# TOP.net
KiCad netlist of a schematic drawn in Altium Designer
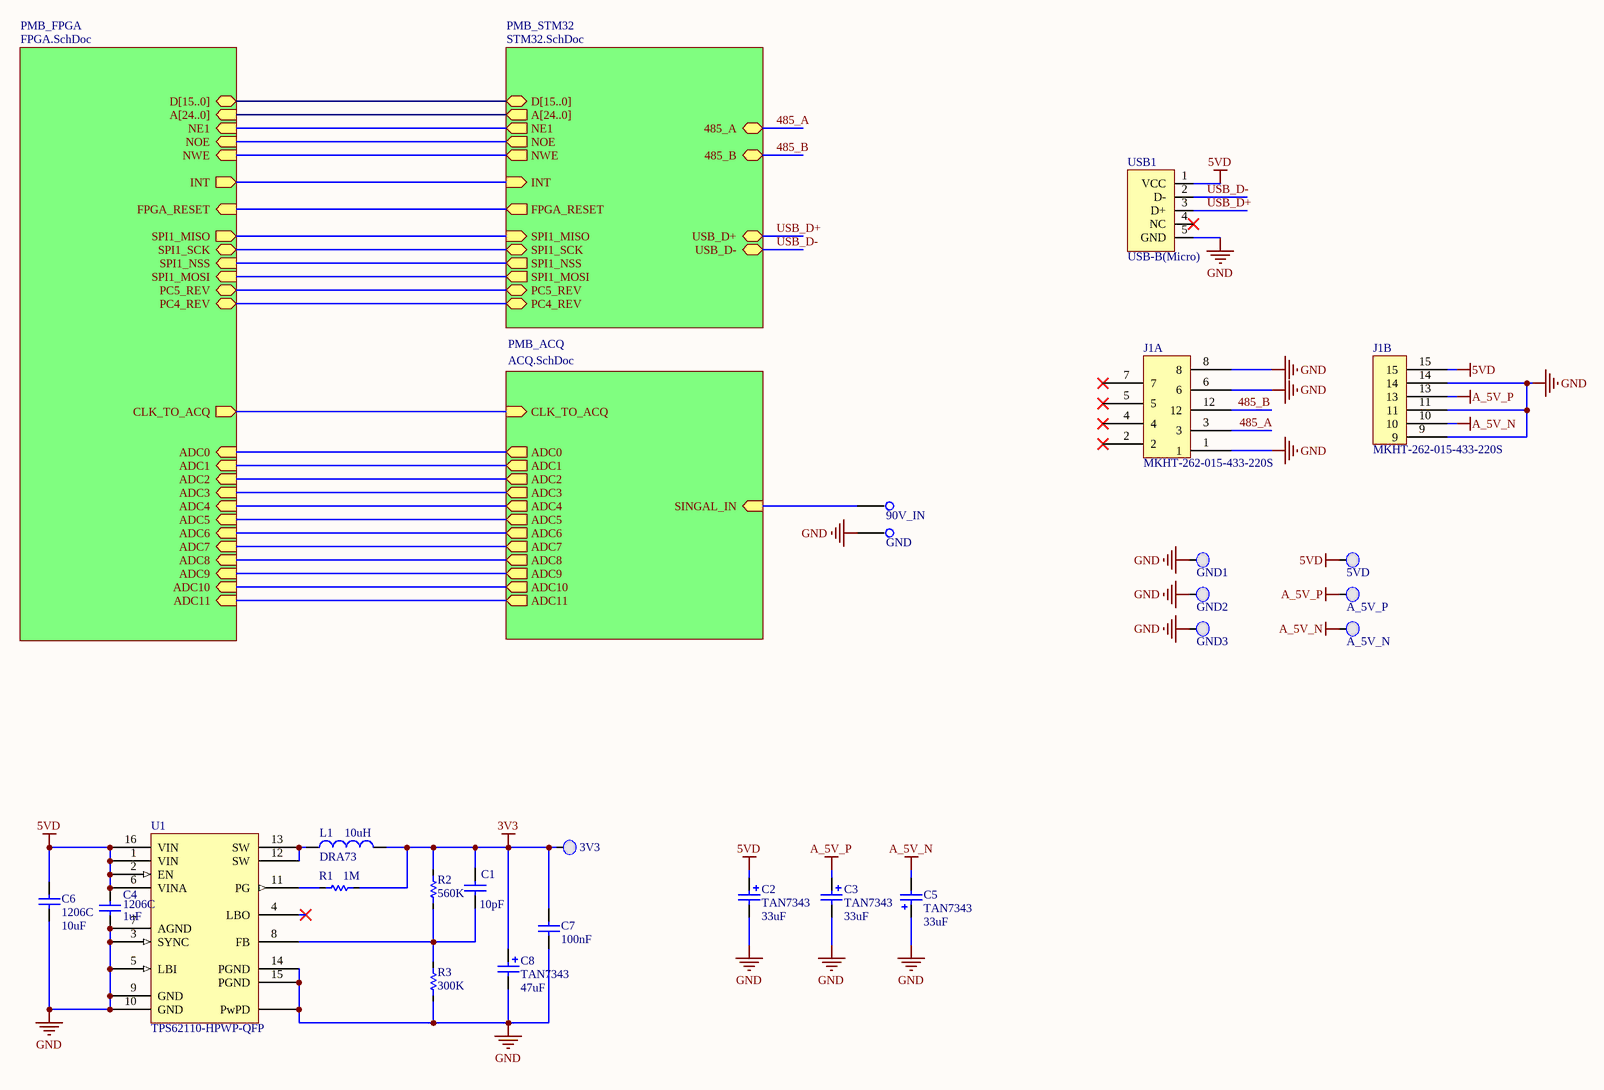
[diagram p0: TOP.SchDoc]

(export (version "E")
  (design (tool "Eeschema 10.0.6"))
  (components
    (comp (ref "3V3") (value "TP") (footprint "TPA") (libsource (lib "STM32") (part "TP")))
    (comp (ref "5VD") (value "TP") (footprint "TPA") (libsource (lib "STM32") (part "TP")))
    (comp (ref "90V_IN") (value "InOut") (footprint "TERMPOWER") (libsource (lib "STM32") (part "InOut")))
    (comp (ref "A_5V_N") (value "TP") (footprint "TPA") (libsource (lib "STM32") (part "TP")))
    (comp (ref "A_5V_P") (value "TP") (footprint "TPA") (libsource (lib "STM32") (part "TP")))
    (comp (ref "C1")
      (value "10pF")
      (footprint "0805C")
      (description "Capacitor")
      (fields (field (name "PUBLISHER") "Altium Limited"))
      (libsource (lib "STM32") (part "Cap"))
    )
    (comp (ref "C2")
      (value "TAN7343")
      (footprint "7343C")
      (description "Polarized Capacitor (Radial)")
      (fields (field (name "ALTIUM_VALUE") "33uF"))
      (libsource (lib "STM32") (part "Cap Pol"))
    )
    (comp (ref "C3")
      (value "TAN7343")
      (footprint "7343C")
      (description "Polarized Capacitor (Radial)")
      (fields (field (name "ALTIUM_VALUE") "33uF"))
      (libsource (lib "STM32") (part "Cap Pol"))
    )
    (comp (ref "C4")
      (value "1uF")
      (footprint "1206C")
      (description "Capacitor")
      (fields (field (name "PACKAGEREFERENCE") "1206C") (field (name "PUBLISHER") "Altium Limited"))
      (libsource (lib "STM32") (part "Cap"))
    )
    (comp (ref "C5")
      (value "TAN7343")
      (footprint "7343C")
      (description "Polarized Capacitor (Radial)")
      (fields (field (name "ALTIUM_VALUE") "33uF"))
      (libsource (lib "STM32") (part "Cap Pol"))
    )
    (comp (ref "C6")
      (value "10uF")
      (footprint "1206C")
      (description "Capacitor")
      (fields (field (name "PACKAGEREFERENCE") "1206C") (field (name "PUBLISHER") "Altium Limited"))
      (libsource (lib "STM32") (part "Cap"))
    )
    (comp (ref "C7")
      (value "100nF")
      (footprint "0805C")
      (description "Capacitor")
      (fields (field (name "PUBLISHER") "Altium Limited"))
      (libsource (lib "STM32") (part "Cap"))
    )
    (comp (ref "C8")
      (value "TAN7343")
      (footprint "7343C")
      (description "Polarized Capacitor (Radial)")
      (fields (field (name "ALTIUM_VALUE") "47uF"))
      (libsource (lib "STM32") (part "Cap Pol"))
    )
    (comp (ref "GND") (value "InOut") (footprint "TERMPOWER") (libsource (lib "STM32") (part "InOut")))
    (comp (ref "GND1") (value "TP") (footprint "TPA") (libsource (lib "STM32") (part "TP")))
    (comp (ref "GND2") (value "TP") (footprint "TPA") (libsource (lib "STM32") (part "TP")))
    (comp (ref "GND3") (value "TP") (footprint "TPA") (libsource (lib "STM32") (part "TP")))
    (comp (ref "J1")
      (value "MKHT-262-015-433-220S")
      (footprint "MKHT-262-015-433-220S")
      (libsource (lib "STM32") (part "MKHT-262-015-433-220S"))
    )
    (comp (ref "L1")
      (value "DRA73")
      (footprint "INDP7676X35N")
      (description "Inductor")
      (fields (field (name "ALTIUM_VALUE") "10uH"))
      (libsource (lib "STM32") (part "Inductor"))
    )
    (comp (ref "R1")
      (value "1M")
      (footprint "0805R")
      (description "Resistor")
      (fields (field (name "PUBLISHER") "Altium Limited"))
      (libsource (lib "STM32") (part "Res1"))
    )
    (comp (ref "R2")
      (value "560K")
      (footprint "0805R")
      (description "Resistor")
      (fields (field (name "PUBLISHER") "Altium Limited"))
      (libsource (lib "STM32") (part "Res1"))
    )
    (comp (ref "R3")
      (value "300K")
      (footprint "0805R")
      (description "Resistor")
      (fields (field (name "PUBLISHER") "Altium Limited"))
      (libsource (lib "STM32") (part "Res1"))
    )
    (comp (ref "U1")
      (value "TPS62110-HPWP-QFP")
      (footprint "PWP16")
      (fields (field (name "PART NUMBER") "Y20033002"))
      (libsource (lib "STM32") (part "TPS62110-HPWP"))
    )
    (comp (ref "USB1")
      (value "USB-B(Micro)")
      (footprint "MICRO-USB-SMD_5P-P0.65-H-F_C10418")
      (libsource (lib "STM32") (part "USB-micro"))
    )
  )
  (nets
    (net (code "1") (name "/485_A") (class "Default")
      (node (ref "J1") (pin "3") (pinfunction "3_3") (pintype "passive"))
    )
    (net (code "2") (name "/485_B") (class "Default")
      (node (ref "J1") (pin "12") (pinfunction "12_12") (pintype "passive"))
    )
    (net (code "25") (name "/SINGAL_IN") (class "Default")
      (node (ref "90V_IN") (pin "1") (pinfunction "NC_1") (pintype "passive"))
    )
    (net (code "30") (name "/USB_D+") (class "Default")
      (node (ref "USB1") (pin "3") (pinfunction "D+_3") (pintype "passive"))
    )
    (net (code "31") (name "/USB_D-") (class "Default")
      (node (ref "USB1") (pin "2") (pinfunction "D-_2") (pintype "passive"))
    )
    (net (code "32") (name "3V3") (class "Default")
      (node (ref "3V3") (pin "1") (pinfunction "TP_1") (pintype "passive"))
      (node (ref "C1") (pin "2") (pinfunction "2_2") (pintype "passive"))
      (node (ref "C7") (pin "2") (pinfunction "2_2") (pintype "passive"))
      (node (ref "C8") (pin "1") (pinfunction "1_1") (pintype "passive"))
      (node (ref "L1") (pin "2") (pinfunction "2_2") (pintype "passive"))
      (node (ref "R1") (pin "2") (pinfunction "2_2") (pintype "passive"))
      (node (ref "R2") (pin "2") (pinfunction "2_2") (pintype "passive"))
    )
    (net (code "33") (name "5VD") (class "Default")
      (node (ref "5VD") (pin "1") (pinfunction "TP_1") (pintype "passive"))
      (node (ref "C2") (pin "1") (pinfunction "1_1") (pintype "passive"))
      (node (ref "C4") (pin "1") (pinfunction "1_1") (pintype "passive"))
      (node (ref "C6") (pin "1") (pinfunction "1_1") (pintype "passive"))
      (node (ref "J1") (pin "15") (pinfunction "15_15") (pintype "passive"))
      (node (ref "U1") (pin "1") (pinfunction "VIN_1") (pintype "power_in"))
      (node (ref "U1") (pin "16") (pinfunction "VIN_16") (pintype "power_in"))
      (node (ref "U1") (pin "2") (pinfunction "EN_2") (pintype "input"))
      (node (ref "U1") (pin "6") (pinfunction "VINA_6") (pintype "power_in"))
      (node (ref "USB1") (pin "1") (pinfunction "VCC_1") (pintype "passive"))
    )
    (net (code "34") (name "A_5V_N") (class "Default")
      (node (ref "A_5V_N") (pin "1") (pinfunction "TP_1") (pintype "passive"))
      (node (ref "C5") (pin "2") (pinfunction "2_2") (pintype "passive"))
      (node (ref "J1") (pin "10") (pinfunction "10_10") (pintype "passive"))
    )
    (net (code "35") (name "A_5V_P") (class "Default")
      (node (ref "A_5V_P") (pin "1") (pinfunction "TP_1") (pintype "passive"))
      (node (ref "C3") (pin "1") (pinfunction "1_1") (pintype "passive"))
      (node (ref "J1") (pin "13") (pinfunction "13_13") (pintype "passive"))
    )
    (net (code "36") (name "GND") (class "Default")
      (node (ref "C2") (pin "2") (pinfunction "2_2") (pintype "passive"))
      (node (ref "C3") (pin "2") (pinfunction "2_2") (pintype "passive"))
      (node (ref "C4") (pin "2") (pinfunction "2_2") (pintype "passive"))
      (node (ref "C5") (pin "1") (pinfunction "1_1") (pintype "passive"))
      (node (ref "C6") (pin "2") (pinfunction "2_2") (pintype "passive"))
      (node (ref "C7") (pin "1") (pinfunction "1_1") (pintype "passive"))
      (node (ref "C8") (pin "2") (pinfunction "2_2") (pintype "passive"))
      (node (ref "GND") (pin "1") (pinfunction "NC_1") (pintype "passive"))
      (node (ref "GND1") (pin "1") (pinfunction "TP_1") (pintype "passive"))
      (node (ref "GND2") (pin "1") (pinfunction "TP_1") (pintype "passive"))
      (node (ref "GND3") (pin "1") (pinfunction "TP_1") (pintype "passive"))
      (node (ref "J1") (pin "1") (pinfunction "1_1") (pintype "passive"))
      (node (ref "J1") (pin "11") (pinfunction "11_11") (pintype "passive"))
      (node (ref "J1") (pin "14") (pinfunction "14_14") (pintype "passive"))
      (node (ref "J1") (pin "6") (pinfunction "6_6") (pintype "passive"))
      (node (ref "J1") (pin "8") (pinfunction "8_8") (pintype "passive"))
      (node (ref "J1") (pin "9") (pinfunction "9_9") (pintype "passive"))
      (node (ref "R3") (pin "1") (pinfunction "1_1") (pintype "passive"))
      (node (ref "U1") (pin "10") (pinfunction "GND_10") (pintype "passive"))
      (node (ref "U1") (pin "14") (pinfunction "PGND_14") (pintype "passive"))
      (node (ref "U1") (pin "15") (pinfunction "PGND_15") (pintype "passive"))
      (node (ref "U1") (pin "3") (pinfunction "SYNC_3") (pintype "input"))
      (node (ref "U1") (pin "5") (pinfunction "LBI_5") (pintype "input"))
      (node (ref "U1") (pin "7") (pinfunction "AGND_7") (pintype "power_in"))
      (node (ref "U1") (pin "9") (pinfunction "GND_9") (pintype "passive"))
      (node (ref "U1") (pin "PwPD") (pinfunction "PwPD_PwPD") (pintype "passive"))
      (node (ref "USB1") (pin "5") (pinfunction "GND_5") (pintype "passive"))
    )
    (net (code "37") (name "Net-(L1-Pad1)") (class "Default")
      (node (ref "L1") (pin "1") (pinfunction "1_1") (pintype "passive"))
      (node (ref "U1") (pin "12") (pinfunction "SW_12") (pintype "passive"))
      (node (ref "U1") (pin "13") (pinfunction "SW_13") (pintype "passive"))
    )
    (net (code "38") (name "Net-(U1-FB)") (class "Default")
      (node (ref "C1") (pin "1") (pinfunction "1_1") (pintype "passive"))
      (node (ref "R2") (pin "1") (pinfunction "1_1") (pintype "passive"))
      (node (ref "R3") (pin "2") (pinfunction "2_2") (pintype "passive"))
      (node (ref "U1") (pin "8") (pinfunction "FB_8") (pintype "passive"))
    )
    (net (code "39") (name "Net-(U1-PG)") (class "Default")
      (node (ref "R1") (pin "1") (pinfunction "1_1") (pintype "passive"))
      (node (ref "U1") (pin "11") (pinfunction "PG_11") (pintype "output"))
    )
    (net (code "40") (name "unconnected-(J1-Pad2)") (class "Default")
      (node (ref "J1") (pin "2") (pinfunction "2_2") (pintype "passive+no_connect"))
    )
    (net (code "41") (name "unconnected-(J1-Pad4)") (class "Default")
      (node (ref "J1") (pin "4") (pinfunction "4_4") (pintype "passive+no_connect"))
    )
    (net (code "42") (name "unconnected-(J1-Pad5)") (class "Default")
      (node (ref "J1") (pin "5") (pinfunction "5_5") (pintype "passive+no_connect"))
    )
    (net (code "43") (name "unconnected-(J1-Pad7)") (class "Default")
      (node (ref "J1") (pin "7") (pinfunction "7_7") (pintype "passive+no_connect"))
    )
    (net (code "44") (name "unconnected-(U1-LBO-Pad4)") (class "Default")
      (node (ref "U1") (pin "4") (pinfunction "LBO_4") (pintype "passive+no_connect"))
    )
    (net (code "45") (name "unconnected-(USB1-NC-Pad4)") (class "Default")
      (node (ref "USB1") (pin "4") (pinfunction "NC_4") (pintype "passive+no_connect"))
    )
  )
)
